# UBC-Thunderbots_PCB_Power__power-v3_1_pc.net
KiCad netlist of a schematic drawn in Altium Designer
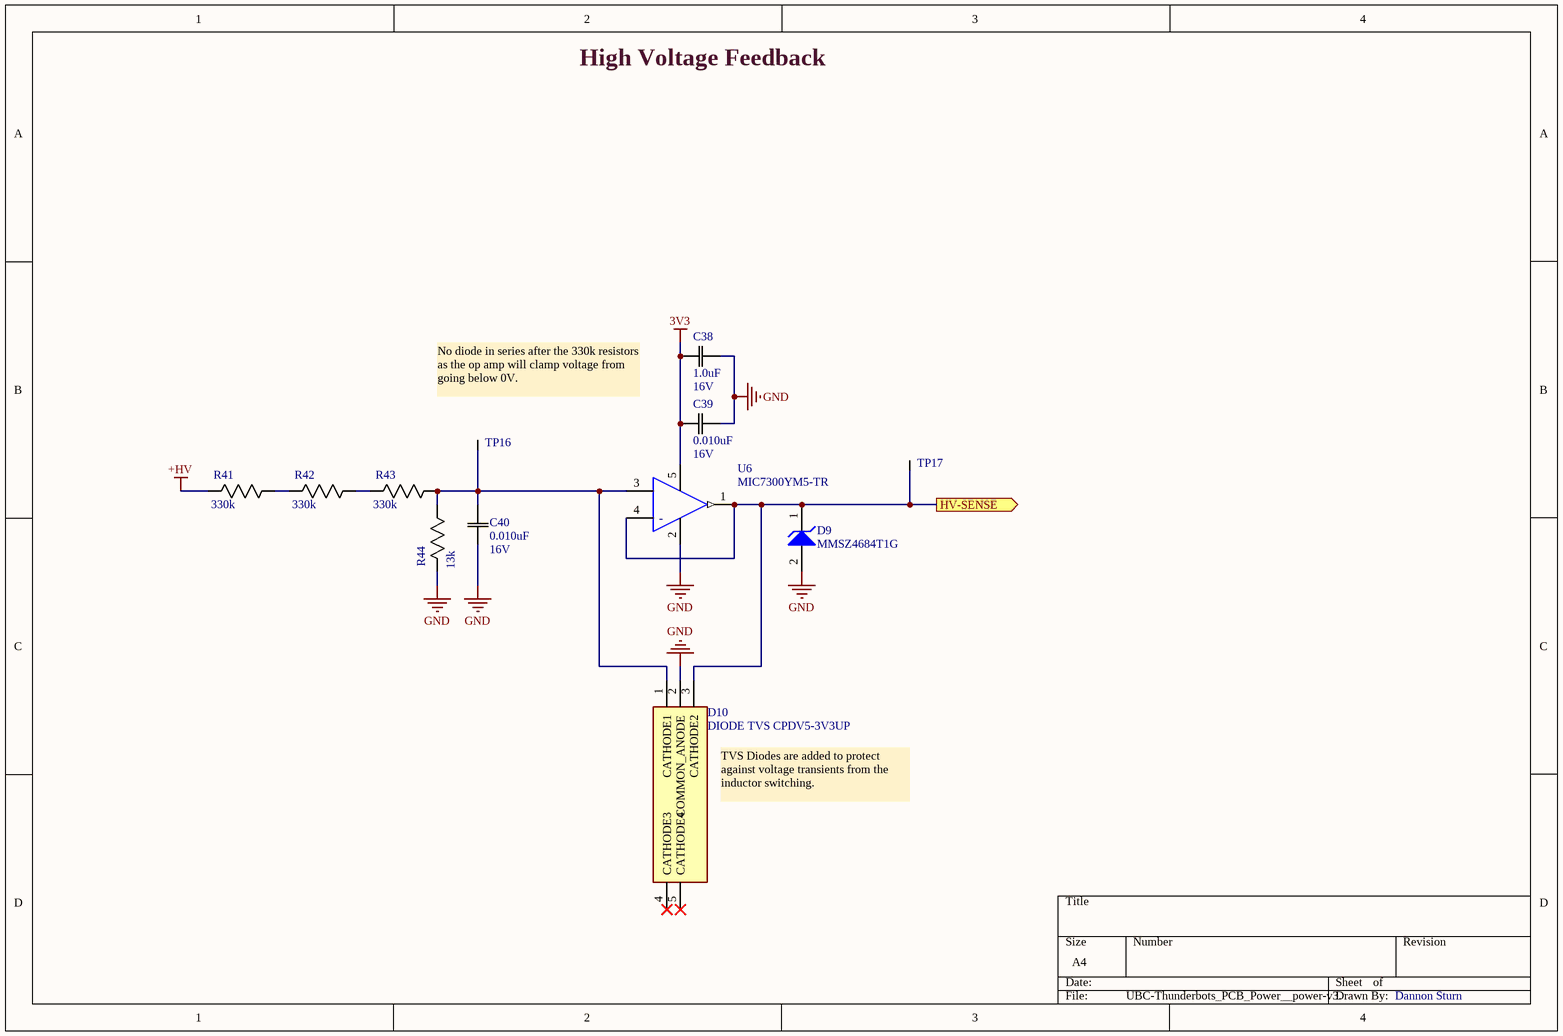
[diagram p0: UBC-Thunderbots_PCB_Power__power-v3.1_pcb__HV-Measurement.SchDoc]

(export (version "E")
  (design (tool "Eeschema 10.0.6"))
  (components
    (comp (ref "C38")
      (value "1.0uF")
      (footprint "0805")
      (description "CAP CER 1.0UF 16V X5R 0603/0805")
      (fields (field (name "TOLERANCE") "10%") (field (name "RATING") "16V"))
      (libsource (lib "AltiumLibraries") (part "CAP 1.0uF 16V"))
    )
    (comp (ref "C39")
      (value "0.010uF")
      (footprint "0805")
      (description "CAP CER 0.010UF 16V X5R 0603/0805")
      (fields (field (name "TOLERANCE") "10%") (field (name "RATING") "16V"))
      (libsource (lib "AltiumLibraries") (part "CAP 0.010uF 16V"))
    )
    (comp (ref "C40")
      (value "0.010uF")
      (footprint "0805")
      (description "CAP CER 0.010UF 16V X5R 0603/0805")
      (fields (field (name "TOLERANCE") "10%") (field (name "RATING") "16V"))
      (libsource (lib "AltiumLibraries") (part "CAP 0.010uF 16V"))
    )
    (comp (ref "D9")
      (value "MMSZ4684T1G")
      (footprint "ONSC-SOD-123-2-425-04_V")
      (description "Zener 3V3 Voltage Regulator, 500 mW, 2-Pin SOD-123, Pb-Free, Tape and Reel")
      (fields (field (name "MANUFACTURER") "On Semiconductor"))
      (libsource (lib "AltiumLibraries") (part "DIODE ZENER 3.3 500mW"))
    )
    (comp (ref "D10")
      (value "DIODE TVS CPDV5-3V3UP")
      (footprint "SOT65P230X110-5N")
      (description "TVS Diode Bidirectional Vbr = 3.5V, Working Voltage = 3.3V")
      (fields
        (field (name "MANUFACTURER_PART_NUMBER") "CPDV5-3V3UP")
        (field (name "MOUSER PART NUMBER") "750-CPDV5-3V3UP")
      )
      (libsource (lib "AltiumLibraries") (part "DIODE TVS CPDV5-3V3UP"))
    )
    (comp (ref "R41")
      (value "330k")
      (footprint "0805")
      (description "RES SMD 330K OHM 5% 1/8W 0805")
      (fields (field (name "TOLERANCE") "5%"))
      (libsource (lib "") (part "RES 330k 1/8W - 5%_1"))
    )
    (comp (ref "R42")
      (value "330k")
      (footprint "0805")
      (description "RES SMD 330K OHM 5% 1/8W 0805")
      (fields (field (name "TOLERANCE") "5%"))
      (libsource (lib "AltiumLibraries") (part "RES 330k 1/8W - 5%"))
    )
    (comp (ref "R43")
      (value "330k")
      (footprint "0805")
      (description "RES SMD 330K OHM 5% 1/8W 0805")
      (fields (field (name "TOLERANCE") "5%"))
      (libsource (lib "AltiumLibraries") (part "RES 330k 1/8W - 5%"))
    )
    (comp (ref "R44")
      (value "13k")
      (footprint "0805")
      (description "RES SMD 13K OHM 5% 1/8W 0805")
      (fields (field (name "TOLERANCE") "5%"))
      (libsource (lib "AltiumLibraries") (part "RES 13k 1/8W"))
    )
    (comp (ref "TP16")
      (value "Test Point (Via)")
      (footprint "TP")
      (libsource (lib "AltiumLibraries") (part "Test Point (Via)"))
    )
    (comp (ref "TP17")
      (value "Test Point (Via)")
      (footprint "TP")
      (libsource (lib "AltiumLibraries") (part "Test Point (Via)"))
    )
    (comp (ref "U6")
      (value "MIC7300YM5-TR")
      (footprint "FP-SOT23-5LD-PL-1-IPC_A")
      (description "IC OPAMP GP 1 CIRCUIT SOT23-5")
      (fields
        (field (name "OCTOPART") "https://octopart.com/mic7300ym5-tr-microchip-66803593")
        (field (name "MANUFACTURER") "Microchip")
      )
      (libsource (lib "AltiumLibraries") (part "OP AMP MIC7300YM5-TR"))
    )
  )
  (nets
    (net (code "1") (name "+HV") (class "Default")
      (node (ref "R41") (pin "2") (pinfunction "R2_2") (pintype "passive"))
    )
    (net (code "2") (name "/HV-SENSE") (class "Default")
      (node (ref "D10") (pin "3") (pinfunction "CATHODE2_3") (pintype "passive"))
      (node (ref "D9") (pin "1") (pinfunction "K_1") (pintype "passive"))
      (node (ref "TP17") (pin "1") (pinfunction "1_1") (pintype "passive"))
      (node (ref "U6") (pin "1") (pinfunction "OUT_1") (pintype "output"))
      (node (ref "U6") (pin "4") (pinfunction "IN-_4") (pintype "tri_state"))
    )
    (net (code "3") (name "3V3") (class "Default")
      (node (ref "C38") (pin "2") (pinfunction "C2_2") (pintype "passive"))
      (node (ref "C39") (pin "1") (pinfunction "C1_1") (pintype "passive"))
      (node (ref "U6") (pin "5") (pinfunction "V+_5") (pintype "power_in"))
    )
    (net (code "4") (name "GND") (class "Default")
      (node (ref "C38") (pin "1") (pinfunction "C1_1") (pintype "passive"))
      (node (ref "C39") (pin "2") (pinfunction "C2_2") (pintype "passive"))
      (node (ref "C40") (pin "1") (pinfunction "C1_1") (pintype "passive"))
      (node (ref "D10") (pin "2") (pinfunction "COMMON_ANODE_2") (pintype "passive"))
      (node (ref "D9") (pin "2") (pinfunction "A_2") (pintype "passive"))
      (node (ref "R44") (pin "2") (pinfunction "R2_2") (pintype "passive"))
      (node (ref "U6") (pin "2") (pinfunction "V-_2") (pintype "power_in"))
    )
    (net (code "5") (name "Net-(C40-C2)") (class "Default")
      (node (ref "C40") (pin "2") (pinfunction "C2_2") (pintype "passive"))
      (node (ref "D10") (pin "1") (pinfunction "CATHODE1_1") (pintype "passive"))
      (node (ref "R43") (pin "1") (pinfunction "R1_1") (pintype "passive"))
      (node (ref "R44") (pin "1") (pinfunction "R1_1") (pintype "passive"))
      (node (ref "TP16") (pin "1") (pinfunction "1_1") (pintype "passive"))
      (node (ref "U6") (pin "3") (pinfunction "IN+_3") (pintype "tri_state"))
    )
    (net (code "6") (name "Net-(R41-R1)") (class "Default")
      (node (ref "R41") (pin "1") (pinfunction "R1_1") (pintype "passive"))
      (node (ref "R42") (pin "2") (pinfunction "R2_2") (pintype "passive"))
    )
    (net (code "7") (name "Net-(R42-R1)") (class "Default")
      (node (ref "R42") (pin "1") (pinfunction "R1_1") (pintype "passive"))
      (node (ref "R43") (pin "2") (pinfunction "R2_2") (pintype "passive"))
    )
    (net (code "8") (name "unconnected-(D10-CATHODE3-Pad4)") (class "Default")
      (node (ref "D10") (pin "4") (pinfunction "CATHODE3_4") (pintype "passive+no_connect"))
    )
    (net (code "9") (name "unconnected-(D10-CATHODE4-Pad5)") (class "Default")
      (node (ref "D10") (pin "5") (pinfunction "CATHODE4_5") (pintype "passive+no_connect"))
    )
  )
)
